# adc_microboard.net
KiCad netlist of a schematic drawn in EAGLE
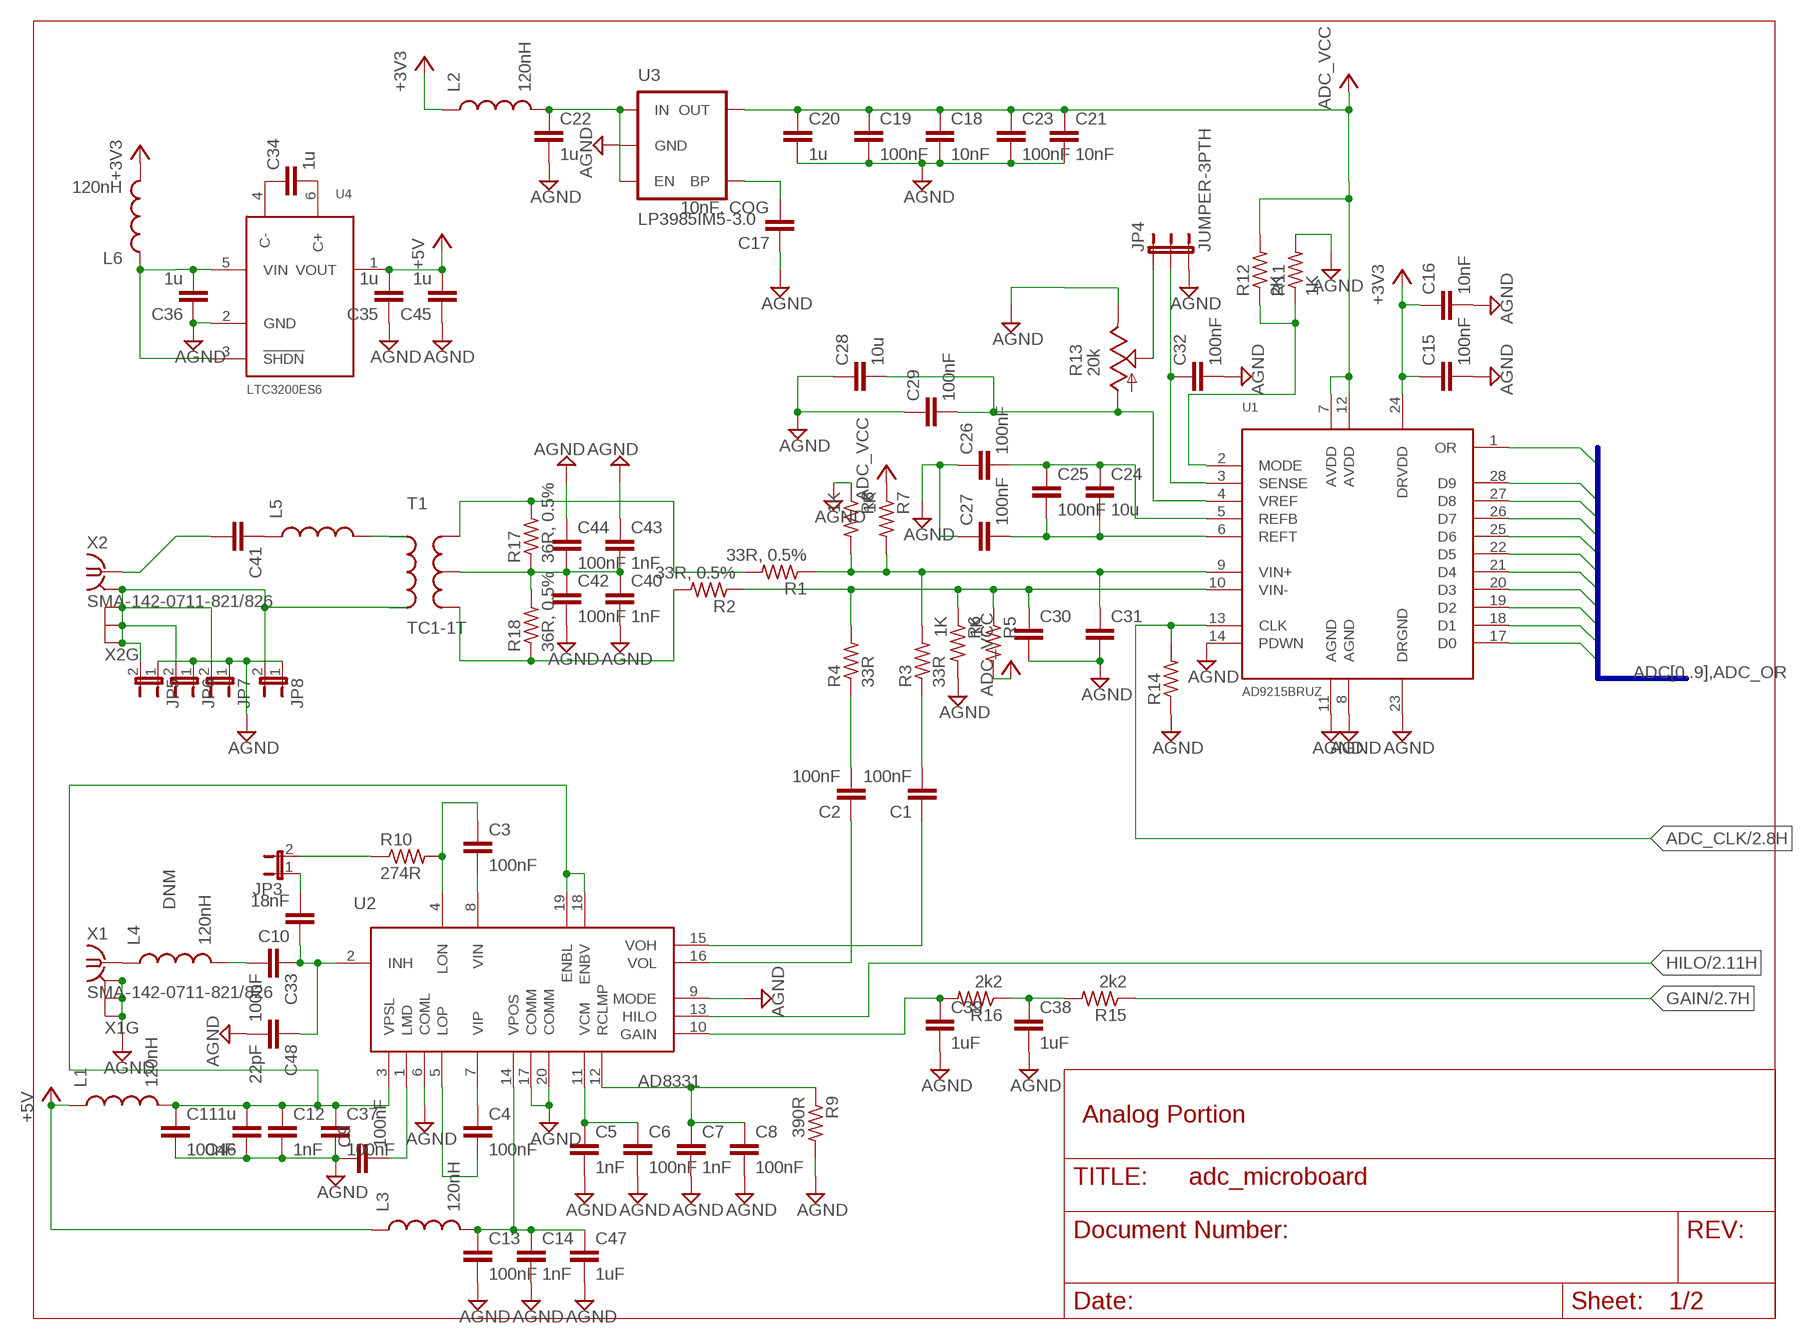
[diagram p0: schematic, sheet 1]
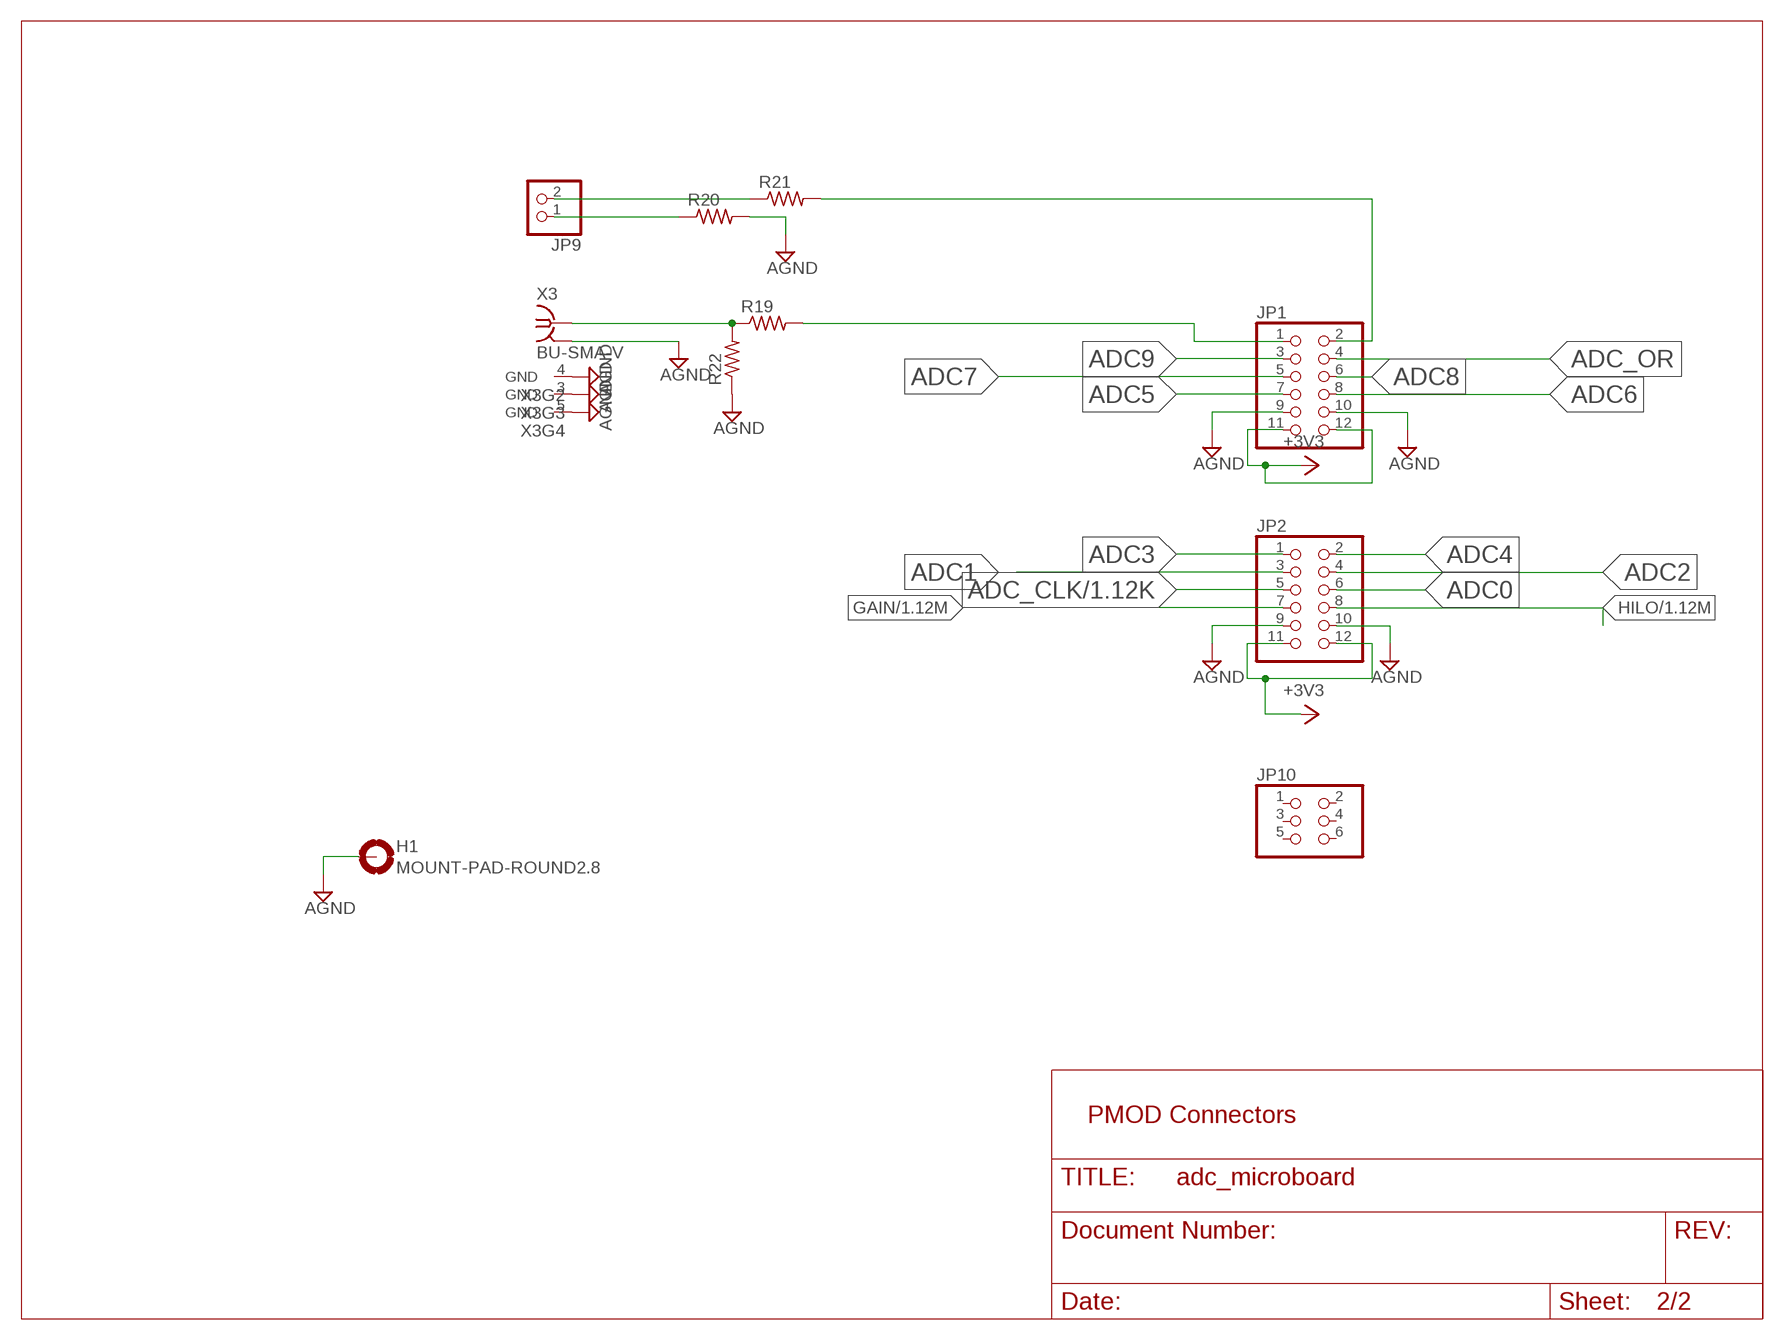
[diagram p1: schematic, sheet 2]

(export (version "E")
  (design (tool "Eeschema 10.0.6"))
  (components
    (comp (ref "C1")
      (value "100nF")
      (footprint "eagle-import:C0603K")
      (libsource (lib "eagle-import") (part "C-EUC0603K"))
    )
    (comp (ref "C2")
      (value "100nF")
      (footprint "eagle-import:C0603K")
      (libsource (lib "eagle-import") (part "C-EUC0603K"))
    )
    (comp (ref "C3")
      (value "100nF")
      (footprint "eagle-import:C0402")
      (libsource (lib "eagle-import") (part "C-EUC0402"))
    )
    (comp (ref "C4")
      (value "100nF")
      (footprint "eagle-import:C0402")
      (libsource (lib "eagle-import") (part "C-EUC0402"))
    )
    (comp (ref "C5")
      (value "1nF")
      (footprint "eagle-import:C0402")
      (fields (field (name "PART#") "C1005X7R1E102K"))
      (libsource (lib "eagle-import") (part "C-EUC0402"))
    )
    (comp (ref "C6")
      (value "100nF")
      (footprint "eagle-import:C0402")
      (fields (field (name "PART#") "GRM155R61A104KA01D"))
      (libsource (lib "eagle-import") (part "C-EUC0402"))
    )
    (comp (ref "C7")
      (value "1nF")
      (footprint "eagle-import:C0402")
      (fields (field (name "PART#") "C1005X7R1E102K"))
      (libsource (lib "eagle-import") (part "C-EUC0402"))
    )
    (comp (ref "C8")
      (value "100nF")
      (footprint "eagle-import:C0402")
      (fields (field (name "PART#") "GRM155R61A104KA01D"))
      (libsource (lib "eagle-import") (part "C-EUC0402"))
    )
    (comp (ref "C9")
      (value "100nF")
      (footprint "eagle-import:C0402")
      (fields (field (name "PART#") "GRM155R61A104KA01D"))
      (libsource (lib "eagle-import") (part "C-EUC0402"))
    )
    (comp (ref "C10")
      (value "18nF")
      (footprint "eagle-import:C0603")
      (libsource (lib "eagle-import") (part "C-EUC0603"))
    )
    (comp (ref "C11")
      (value "100nF")
      (footprint "eagle-import:C0402")
      (fields (field (name "PART#") "GRM155R61A104KA01D"))
      (libsource (lib "eagle-import") (part "C-EUC0402"))
    )
    (comp (ref "C12")
      (value "1nF")
      (footprint "eagle-import:C0402")
      (fields (field (name "PART#") "C1005X7R1E102K"))
      (libsource (lib "eagle-import") (part "C-EUC0402"))
    )
    (comp (ref "C13")
      (value "100nF")
      (footprint "eagle-import:C0402")
      (fields (field (name "PART#") "GRM155R61A104KA01D"))
      (libsource (lib "eagle-import") (part "C-EUC0402"))
    )
    (comp (ref "C14")
      (value "1nF")
      (footprint "eagle-import:C0402")
      (fields (field (name "PART#") "C1005X7R1E102K"))
      (libsource (lib "eagle-import") (part "C-EUC0402"))
    )
    (comp (ref "C15")
      (value "100nF")
      (footprint "eagle-import:C0402")
      (fields (field (name "PART#") "GRM155R61A104KA01D"))
      (libsource (lib "eagle-import") (part "C-EUC0402"))
    )
    (comp (ref "C16")
      (value "10nF")
      (footprint "eagle-import:C0402")
      (libsource (lib "eagle-import") (part "C-EUC0402"))
    )
    (comp (ref "C17")
      (value "10nF, COG")
      (footprint "eagle-import:C0402")
      (libsource (lib "eagle-import") (part "C-EUC0402"))
    )
    (comp (ref "C18")
      (value "10nF")
      (footprint "eagle-import:C0402")
      (fields (field (name "PART#") "GRM155R71E103KA01D"))
      (libsource (lib "eagle-import") (part "C-EUC0402"))
    )
    (comp (ref "C19")
      (value "100nF")
      (footprint "eagle-import:C0402")
      (fields (field (name "PART#") "GRM155R61A104KA01D"))
      (libsource (lib "eagle-import") (part "C-EUC0402"))
    )
    (comp (ref "C20")
      (value "1u")
      (footprint "eagle-import:C0603")
      (fields (field (name "PART#") "GRM188R61A105KA61D"))
      (libsource (lib "eagle-import") (part "C-EUC0603"))
    )
    (comp (ref "C21")
      (value "10nF")
      (footprint "eagle-import:C0402")
      (fields (field (name "PART#") "GRM155R71E103KA01D"))
      (libsource (lib "eagle-import") (part "C-EUC0402"))
    )
    (comp (ref "C22")
      (value "1u")
      (footprint "eagle-import:C0603")
      (fields (field (name "PART#") "GRM188R61A105KA61D"))
      (libsource (lib "eagle-import") (part "C-EUC0603"))
    )
    (comp (ref "C23")
      (value "100nF")
      (footprint "eagle-import:C0402")
      (fields (field (name "PART#") "GRM155R61A104KA01D"))
      (libsource (lib "eagle-import") (part "C-EUC0402"))
    )
    (comp (ref "C24")
      (value "10u")
      (footprint "eagle-import:C0603")
      (libsource (lib "eagle-import") (part "C-EUC0603"))
    )
    (comp (ref "C25")
      (value "100nF")
      (footprint "eagle-import:C0402")
      (fields (field (name "PART#") "GRM155R61A104KA01D"))
      (libsource (lib "eagle-import") (part "C-EUC0402"))
    )
    (comp (ref "C26")
      (value "100nF")
      (footprint "eagle-import:C0402")
      (fields (field (name "PART#") "GRM155R61A104KA01D"))
      (libsource (lib "eagle-import") (part "C-EUC0402"))
    )
    (comp (ref "C27")
      (value "100nF")
      (footprint "eagle-import:C0402")
      (fields (field (name "PART#") "GRM155R61A104KA01D"))
      (libsource (lib "eagle-import") (part "C-EUC0402"))
    )
    (comp (ref "C28")
      (value "10u")
      (footprint "eagle-import:C0603")
      (libsource (lib "eagle-import") (part "C-EUC0603"))
    )
    (comp (ref "C29")
      (value "100nF")
      (footprint "eagle-import:C0402")
      (fields (field (name "PART#") "GRM155R61A104KA01D"))
      (libsource (lib "eagle-import") (part "C-EUC0402"))
    )
    (comp (ref "C30")
      (value "C-EUC0402")
      (footprint "eagle-import:C0402")
      (libsource (lib "eagle-import") (part "C-EUC0402"))
    )
    (comp (ref "C31")
      (value "C-EUC0402")
      (footprint "eagle-import:C0402")
      (libsource (lib "eagle-import") (part "C-EUC0402"))
    )
    (comp (ref "C32")
      (value "100nF")
      (footprint "eagle-import:C0402")
      (fields (field (name "PART#") "GRM155R61A104KA01D"))
      (libsource (lib "eagle-import") (part "C-EUC0402"))
    )
    (comp (ref "C33")
      (value "100nF")
      (footprint "eagle-import:C0603K")
      (libsource (lib "eagle-import") (part "C-EUC0603K"))
    )
    (comp (ref "C34")
      (value "1u")
      (footprint "eagle-import:C0603")
      (fields (field (name "PART#") "GRM188R61A105KA61D"))
      (libsource (lib "eagle-import") (part "C-EUC0603"))
    )
    (comp (ref "C35")
      (value "1u")
      (footprint "eagle-import:C0603")
      (fields (field (name "PART#") "GRM188R61A105KA61D"))
      (libsource (lib "eagle-import") (part "C-EUC0603"))
    )
    (comp (ref "C36")
      (value "1u")
      (footprint "eagle-import:C0603")
      (fields (field (name "PART#") "GRM188R61A105KA61D"))
      (libsource (lib "eagle-import") (part "C-EUC0603"))
    )
    (comp (ref "C37")
      (value "100nF")
      (footprint "eagle-import:C0402")
      (fields (field (name "PART#") "GRM155R61A104KA01D"))
      (libsource (lib "eagle-import") (part "C-EUC0402"))
    )
    (comp (ref "C38")
      (value "1uF")
      (footprint "eagle-import:C0603")
      (libsource (lib "eagle-import") (part "C-EUC0603"))
    )
    (comp (ref "C39")
      (value "1uF")
      (footprint "eagle-import:C0603")
      (libsource (lib "eagle-import") (part "C-EUC0603"))
    )
    (comp (ref "C40")
      (value "1nF")
      (footprint "eagle-import:C0402")
      (fields (field (name "PART#") "C1005X7R1E102K"))
      (libsource (lib "eagle-import") (part "C-EUC0402"))
    )
    (comp (ref "C41")
      (value "C-EUC0603K")
      (footprint "eagle-import:C0603K")
      (libsource (lib "eagle-import") (part "C-EUC0603K"))
    )
    (comp (ref "C42")
      (value "100nF")
      (footprint "eagle-import:C0402")
      (fields (field (name "PART#") "GRM155R61A104KA01D"))
      (libsource (lib "eagle-import") (part "C-EUC0402"))
    )
    (comp (ref "C43")
      (value "1nF")
      (footprint "eagle-import:C0402")
      (fields (field (name "PART#") "C1005X7R1E102K"))
      (libsource (lib "eagle-import") (part "C-EUC0402"))
    )
    (comp (ref "C44")
      (value "100nF")
      (footprint "eagle-import:C0402")
      (fields (field (name "PART#") "GRM155R61A104KA01D"))
      (libsource (lib "eagle-import") (part "C-EUC0402"))
    )
    (comp (ref "C45")
      (value "1u")
      (footprint "eagle-import:C0603")
      (fields (field (name "PART#") "GRM188R61A105KA61D"))
      (libsource (lib "eagle-import") (part "C-EUC0603"))
    )
    (comp (ref "C46")
      (value "1u")
      (footprint "eagle-import:C0402")
      (fields (field (name "PART#") "GRM188R61A105KA61D"))
      (libsource (lib "eagle-import") (part "C-EUC0402"))
    )
    (comp (ref "C47")
      (value "1uF")
      (footprint "eagle-import:C0402")
      (fields (field (name "PART#") "C1005X7R1E102K"))
      (libsource (lib "eagle-import") (part "C-EUC0402"))
    )
    (comp (ref "C48")
      (value "22pF")
      (footprint "eagle-import:C0603")
      (libsource (lib "eagle-import") (part "C-EUC0603"))
    )
    (comp (ref "JP3")
      (value "JUMPER-2SMD-NC")
      (footprint "eagle-import:SJ_2S")
      (libsource (lib "eagle-import") (part "JUMPER-2SMD-NC"))
    )
    (comp (ref "JP4")
      (value "JUMPER-3PTH")
      (footprint "eagle-import:1X03")
      (libsource (lib "eagle-import") (part "JUMPER-3PTH"))
    )
    (comp (ref "JP5")
      (value "JUMPER-2SMD-NC")
      (footprint "eagle-import:SJ_2S")
      (libsource (lib "eagle-import") (part "JUMPER-2SMD-NC"))
    )
    (comp (ref "JP6")
      (value "JUMPER-2SMD-NC")
      (footprint "eagle-import:SJ_2S")
      (libsource (lib "eagle-import") (part "JUMPER-2SMD-NC"))
    )
    (comp (ref "JP7")
      (value "JUMPER-2SMD-NC")
      (footprint "eagle-import:SJ_2S")
      (libsource (lib "eagle-import") (part "JUMPER-2SMD-NC"))
    )
    (comp (ref "JP8")
      (value "JUMPER-2SMD-NC")
      (footprint "eagle-import:SJ_2S")
      (libsource (lib "eagle-import") (part "JUMPER-2SMD-NC"))
    )
    (comp (ref "L1")
      (value "120nH")
      (footprint "eagle-import:0603")
      (fields (field (name "PART#") "MLF1608DR12M"))
      (libsource (lib "eagle-import") (part "INDUCTOR0603"))
    )
    (comp (ref "L2")
      (value "120nH")
      (footprint "eagle-import:0603")
      (libsource (lib "eagle-import") (part "INDUCTOR0603"))
    )
    (comp (ref "L3")
      (value "120nH")
      (footprint "eagle-import:0603")
      (libsource (lib "eagle-import") (part "INDUCTOR0603"))
    )
    (comp (ref "L4")
      (value "120nH")
      (footprint "eagle-import:0603")
      (libsource (lib "eagle-import") (part "INDUCTOR0603"))
    )
    (comp (ref "L5")
      (value "INDUCTOR0603")
      (footprint "eagle-import:0603")
      (libsource (lib "eagle-import") (part "INDUCTOR0603"))
    )
    (comp (ref "L6")
      (value "120nH")
      (footprint "eagle-import:0603")
      (libsource (lib "eagle-import") (part "INDUCTOR0603"))
    )
    (comp (ref "R1")
      (value "33R, 0.5%")
      (footprint "eagle-import:R0603")
      (libsource (lib "eagle-import") (part "R-US_R0603"))
    )
    (comp (ref "R2")
      (value "33R, 0.5%")
      (footprint "eagle-import:R0603")
      (libsource (lib "eagle-import") (part "R-US_R0603"))
    )
    (comp (ref "R3")
      (value "33R")
      (footprint "eagle-import:R0603")
      (libsource (lib "eagle-import") (part "R-US_R0603"))
    )
    (comp (ref "R4")
      (value "33R")
      (footprint "eagle-import:R0603")
      (libsource (lib "eagle-import") (part "R-US_R0603"))
    )
    (comp (ref "R5")
      (value "1K")
      (footprint "eagle-import:R0402")
      (libsource (lib "eagle-import") (part "R-US_R0402"))
    )
    (comp (ref "R6")
      (value "1K")
      (footprint "eagle-import:R0402")
      (libsource (lib "eagle-import") (part "R-US_R0402"))
    )
    (comp (ref "R7")
      (value "1K")
      (footprint "eagle-import:R0402")
      (libsource (lib "eagle-import") (part "R-US_R0402"))
    )
    (comp (ref "R8")
      (value "1K")
      (footprint "eagle-import:R0402")
      (libsource (lib "eagle-import") (part "R-US_R0402"))
    )
    (comp (ref "R9")
      (value "390R")
      (footprint "eagle-import:R0603")
      (libsource (lib "eagle-import") (part "R-US_R0603"))
    )
    (comp (ref "R10")
      (value "274R")
      (footprint "eagle-import:R0603")
      (libsource (lib "eagle-import") (part "R-US_R0603"))
    )
    (comp (ref "R11")
      (value "1K")
      (footprint "eagle-import:R0402")
      (libsource (lib "eagle-import") (part "R-US_R0402"))
    )
    (comp (ref "R12")
      (value "2K")
      (footprint "eagle-import:R0603")
      (libsource (lib "eagle-import") (part "R-US_R0603"))
    )
    (comp (ref "R13")
      (value "20k")
      (footprint "eagle-import:3361P")
      (fields (field (name "PART#") "3361P-1-203GLF"))
      (libsource (lib "eagle-import") (part "TRIM_US-3361P"))
    )
    (comp (ref "R14")
      (value "R-US_R0603")
      (footprint "eagle-import:R0603")
      (libsource (lib "eagle-import") (part "R-US_R0603"))
    )
    (comp (ref "R15")
      (value "2k2")
      (footprint "eagle-import:R0603")
      (libsource (lib "eagle-import") (part "R-US_R0603"))
    )
    (comp (ref "R16")
      (value "2k2")
      (footprint "eagle-import:R0603")
      (libsource (lib "eagle-import") (part "R-US_R0603"))
    )
    (comp (ref "R17")
      (value "36R, 0.5%")
      (footprint "eagle-import:R0603")
      (libsource (lib "eagle-import") (part "R-US_R0603"))
    )
    (comp (ref "R18")
      (value "36R, 0.5%")
      (footprint "eagle-import:R0603")
      (libsource (lib "eagle-import") (part "R-US_R0603"))
    )
    (comp (ref "T1")
      (value "TC1-1T")
      (footprint "eagle-import:AT224-1A")
      (libsource (lib "eagle-import") (part "TC1-1T"))
    )
    (comp (ref "U1")
      (value "AD9215BRUZ")
      (footprint "eagle-import:TSSOP28")
      (libsource (lib "eagle-import") (part "AD9215BRUZ"))
    )
    (comp (ref "U2")
      (value "AD8331")
      (footprint "eagle-import:QSOP20")
      (fields (field (name "PART#") "AD8331ARQZ"))
      (libsource (lib "eagle-import") (part "AD8331"))
    )
    (comp (ref "U3")
      (value "LP3985IM5-3.0")
      (footprint "eagle-import:SOT23-5")
      (libsource (lib "eagle-import") (part "V_REG_LDOSMD"))
    )
    (comp (ref "U4")
      (value "LTC3200ES6")
      (footprint "eagle-import:SOT23-6L")
      (fields (field (name "PART#") "LTC3200ES6-5#TRMPBF"))
      (libsource (lib "eagle-import") (part "LTC3200ES6"))
    )
    (comp (ref "X1")
      (value "SMA-142-0711-821/826")
      (footprint "eagle-import:J502-ND-142-0711-821_826")
      (fields
        (field (name "MF") "JOHNSON COMPONENTS")
        (field (name "MPN") "142-0711-821")
        (field (name "DIGIKEY#") "CONSMA003.062-ND")
      )
      (libsource (lib "eagle-import") (part "SMA-142-0711-821/826"))
    )
    (comp (ref "X2")
      (value "SMA-142-0711-821/826")
      (footprint "eagle-import:J502-ND-142-0711-821_826")
      (fields
        (field (name "MF") "JOHNSON COMPONENTS")
        (field (name "MPN") "142-0711-821")
        (field (name "DIGIKEY#") "CONSMA003.062-ND")
      )
      (libsource (lib "eagle-import") (part "SMA-142-0711-821/826"))
    )
    (comp (ref "H1")
      (value "MOUNT-PAD-ROUND2.8")
      (footprint "eagle-import:2,8-PAD")
      (libsource (lib "eagle-import") (part "MOUNT-PAD-ROUND2.8"))
    )
    (comp (ref "JP1")
      (value "PINHD-2X6")
      (footprint "eagle-import:2X06")
      (libsource (lib "eagle-import") (part "PINHD-2X6"))
    )
    (comp (ref "JP2")
      (value "PINHD-2X6")
      (footprint "eagle-import:2X06")
      (libsource (lib "eagle-import") (part "PINHD-2X6"))
    )
    (comp (ref "JP9")
      (value "PINHD-1X2/90")
      (footprint "eagle-import:1X02_90")
      (libsource (lib "eagle-import") (part "PINHD-1X2/90"))
    )
    (comp (ref "JP10")
      (value "PINHD-2X3")
      (footprint "eagle-import:2X03")
      (libsource (lib "eagle-import") (part "PINHD-2X3"))
    )
    (comp (ref "R19")
      (value "R-US_R0603")
      (footprint "eagle-import:R0603")
      (libsource (lib "eagle-import") (part "R-US_R0603"))
    )
    (comp (ref "R20")
      (value "R-US_R0603")
      (footprint "eagle-import:R0603")
      (libsource (lib "eagle-import") (part "R-US_R0603"))
    )
    (comp (ref "R21")
      (value "R-US_R0603")
      (footprint "eagle-import:R0603")
      (libsource (lib "eagle-import") (part "R-US_R0603"))
    )
    (comp (ref "R22")
      (value "R-US_R0603")
      (footprint "eagle-import:R0603")
      (libsource (lib "eagle-import") (part "R-US_R0603"))
    )
    (comp (ref "X3")
      (value "BU-SMA-V")
      (footprint "eagle-import:BU-SMA-V")
      (libsource (lib "eagle-import") (part "BU-SMA-V"))
    )
  )
  (nets
    (net (code "1") (name "+3V3") (class "Default")
      (node (ref "C15") (pin "1") (pinfunction "1_1") (pintype "passive"))
      (node (ref "C16") (pin "1") (pinfunction "1_1") (pintype "passive"))
      (node (ref "JP1") (pin "11") (pinfunction "11_11") (pintype "passive"))
      (node (ref "JP1") (pin "12") (pinfunction "12_12") (pintype "passive"))
      (node (ref "JP2") (pin "11") (pinfunction "11_11") (pintype "passive"))
      (node (ref "JP2") (pin "12") (pinfunction "12_12") (pintype "passive"))
      (node (ref "L2") (pin "1") (pinfunction "1_1") (pintype "passive"))
      (node (ref "L6") (pin "2") (pinfunction "2_2") (pintype "passive"))
      (node (ref "U1") (pin "24") (pinfunction "DRVDD_24") (pintype "bidirectional"))
    )
    (net (code "2") (name "+5V") (class "Default")
      (node (ref "C35") (pin "2") (pinfunction "2_2") (pintype "passive"))
      (node (ref "C45") (pin "2") (pinfunction "2_2") (pintype "passive"))
      (node (ref "L1") (pin "1") (pinfunction "1_1") (pintype "passive"))
      (node (ref "L3") (pin "1") (pinfunction "1_1") (pintype "passive"))
      (node (ref "U4") (pin "1") (pinfunction "VOUT_1") (pintype "bidirectional"))
    )
    (net (code "4") (name "ADC0") (class "Default")
      (node (ref "JP2") (pin "6") (pinfunction "6_6") (pintype "passive"))
      (node (ref "U1") (pin "17") (pinfunction "D0_17") (pintype "bidirectional"))
    )
    (net (code "5") (name "ADC1") (class "Default")
      (node (ref "JP2") (pin "3") (pinfunction "3_3") (pintype "passive"))
      (node (ref "U1") (pin "18") (pinfunction "D1_18") (pintype "bidirectional"))
    )
    (net (code "6") (name "ADC2") (class "Default")
      (node (ref "JP2") (pin "4") (pinfunction "4_4") (pintype "passive"))
      (node (ref "U1") (pin "19") (pinfunction "D2_19") (pintype "bidirectional"))
    )
    (net (code "7") (name "ADC3") (class "Default")
      (node (ref "JP2") (pin "1") (pinfunction "1_1") (pintype "passive"))
      (node (ref "U1") (pin "20") (pinfunction "D3_20") (pintype "bidirectional"))
    )
    (net (code "8") (name "ADC4") (class "Default")
      (node (ref "JP2") (pin "2") (pinfunction "2_2") (pintype "passive"))
      (node (ref "U1") (pin "21") (pinfunction "D4_21") (pintype "bidirectional"))
    )
    (net (code "9") (name "ADC5") (class "Default")
      (node (ref "JP1") (pin "7") (pinfunction "7_7") (pintype "passive"))
      (node (ref "U1") (pin "22") (pinfunction "D5_22") (pintype "bidirectional"))
    )
    (net (code "10") (name "ADC6") (class "Default")
      (node (ref "JP1") (pin "8") (pinfunction "8_8") (pintype "passive"))
      (node (ref "U1") (pin "25") (pinfunction "D6_25") (pintype "bidirectional"))
    )
    (net (code "11") (name "ADC7") (class "Default")
      (node (ref "JP1") (pin "5") (pinfunction "5_5") (pintype "passive"))
      (node (ref "U1") (pin "26") (pinfunction "D7_26") (pintype "bidirectional"))
    )
    (net (code "12") (name "ADC8") (class "Default")
      (node (ref "JP1") (pin "6") (pinfunction "6_6") (pintype "passive"))
      (node (ref "U1") (pin "27") (pinfunction "D8_27") (pintype "bidirectional"))
    )
    (net (code "13") (name "ADC9") (class "Default")
      (node (ref "JP1") (pin "3") (pinfunction "3_3") (pintype "passive"))
      (node (ref "U1") (pin "28") (pinfunction "D9_28") (pintype "bidirectional"))
    )
    (net (code "14") (name "ADC_CLK") (class "Default")
      (node (ref "JP2") (pin "5") (pinfunction "5_5") (pintype "passive"))
      (node (ref "R14") (pin "2") (pinfunction "2_2") (pintype "passive"))
      (node (ref "U1") (pin "13") (pinfunction "CLK_13") (pintype "bidirectional"))
    )
    (net (code "15") (name "ADC_OR") (class "Default")
      (node (ref "JP1") (pin "4") (pinfunction "4_4") (pintype "passive"))
      (node (ref "U1") (pin "1") (pinfunction "OR_1") (pintype "bidirectional"))
    )
    (net (code "16") (name "ADC_VCC") (class "Default")
      (node (ref "C18") (pin "1") (pinfunction "1_1") (pintype "passive"))
      (node (ref "C19") (pin "1") (pinfunction "1_1") (pintype "passive"))
      (node (ref "C20") (pin "1") (pinfunction "1_1") (pintype "passive"))
      (node (ref "C21") (pin "1") (pinfunction "1_1") (pintype "passive"))
      (node (ref "C23") (pin "1") (pinfunction "1_1") (pintype "passive"))
      (node (ref "R12") (pin "2") (pinfunction "2_2") (pintype "passive"))
      (node (ref "R5") (pin "2") (pinfunction "2_2") (pintype "passive"))
      (node (ref "R7") (pin "1") (pinfunction "1_1") (pintype "passive"))
      (node (ref "U1") (pin "12") (pinfunction "AVDD_12") (pintype "bidirectional"))
      (node (ref "U1") (pin "7") (pinfunction "AVDD_7") (pintype "bidirectional"))
      (node (ref "U3") (pin "5") (pinfunction "OUT_5") (pintype "passive"))
    )
    (net (code "17") (name "AGND") (class "Default")
      (node (ref "C11") (pin "2") (pinfunction "2_2") (pintype "passive"))
      (node (ref "C12") (pin "2") (pinfunction "2_2") (pintype "passive"))
      (node (ref "C13") (pin "2") (pinfunction "2_2") (pintype "passive"))
      (node (ref "C14") (pin "2") (pinfunction "2_2") (pintype "passive"))
      (node (ref "C15") (pin "2") (pinfunction "2_2") (pintype "passive"))
      (node (ref "C16") (pin "2") (pinfunction "2_2") (pintype "passive"))
      (node (ref "C17") (pin "1") (pinfunction "1_1") (pintype "passive"))
      (node (ref "C18") (pin "2") (pinfunction "2_2") (pintype "passive"))
      (node (ref "C19") (pin "2") (pinfunction "2_2") (pintype "passive"))
      (node (ref "C20") (pin "2") (pinfunction "2_2") (pintype "passive"))
      (node (ref "C21") (pin "2") (pinfunction "2_2") (pintype "passive"))
      (node (ref "C22") (pin "2") (pinfunction "2_2") (pintype "passive"))
      (node (ref "C23") (pin "2") (pinfunction "2_2") (pintype "passive"))
      (node (ref "C26") (pin "1") (pinfunction "1_1") (pintype "passive"))
      (node (ref "C27") (pin "1") (pinfunction "1_1") (pintype "passive"))
      (node (ref "C28") (pin "1") (pinfunction "1_1") (pintype "passive"))
      (node (ref "C29") (pin "1") (pinfunction "1_1") (pintype "passive"))
      (node (ref "C30") (pin "2") (pinfunction "2_2") (pintype "passive"))
      (node (ref "C31") (pin "2") (pinfunction "2_2") (pintype "passive"))
      (node (ref "C32") (pin "2") (pinfunction "2_2") (pintype "passive"))
      (node (ref "C35") (pin "1") (pinfunction "1_1") (pintype "passive"))
      (node (ref "C36") (pin "1") (pinfunction "1_1") (pintype "passive"))
      (node (ref "C37") (pin "2") (pinfunction "2_2") (pintype "passive"))
      (node (ref "C38") (pin "2") (pinfunction "2_2") (pintype "passive"))
      (node (ref "C39") (pin "2") (pinfunction "2_2") (pintype "passive"))
      (node (ref "C40") (pin "2") (pinfunction "2_2") (pintype "passive"))
      (node (ref "C42") (pin "2") (pinfunction "2_2") (pintype "passive"))
      (node (ref "C43") (pin "1") (pinfunction "1_1") (pintype "passive"))
      (node (ref "C44") (pin "1") (pinfunction "1_1") (pintype "passive"))
      (node (ref "C45") (pin "1") (pinfunction "1_1") (pintype "passive"))
      (node (ref "C46") (pin "1") (pinfunction "1_1") (pintype "passive"))
      (node (ref "C47") (pin "2") (pinfunction "2_2") (pintype "passive"))
      (node (ref "C48") (pin "2") (pinfunction "2_2") (pintype "passive"))
      (node (ref "C5") (pin "2") (pinfunction "2_2") (pintype "passive"))
      (node (ref "C6") (pin "2") (pinfunction "2_2") (pintype "passive"))
      (node (ref "C7") (pin "2") (pinfunction "2_2") (pintype "passive"))
      (node (ref "C8") (pin "2") (pinfunction "2_2") (pintype "passive"))
      (node (ref "C9") (pin "1") (pinfunction "1_1") (pintype "passive"))
      (node (ref "H1") (pin "B2,8") (pinfunction "MOUNT_B2,8") (pintype "passive"))
      (node (ref "JP1") (pin "10") (pinfunction "10_10") (pintype "passive"))
      (node (ref "JP1") (pin "9") (pinfunction "9_9") (pintype "passive"))
      (node (ref "JP2") (pin "10") (pinfunction "10_10") (pintype "passive"))
      (node (ref "JP2") (pin "9") (pinfunction "9_9") (pintype "passive"))
      (node (ref "JP4") (pin "3") (pinfunction "3_3") (pintype "passive"))
      (node (ref "JP5") (pin "1") (pinfunction "1_1") (pintype "passive"))
      (node (ref "JP6") (pin "1") (pinfunction "1_1") (pintype "passive"))
      (node (ref "JP7") (pin "1") (pinfunction "1_1") (pintype "passive"))
      (node (ref "JP8") (pin "1") (pinfunction "1_1") (pintype "passive"))
      (node (ref "R11") (pin "2") (pinfunction "2_2") (pintype "passive"))
      (node (ref "R13") (pin "1") (pinfunction "E_1") (pintype "passive"))
      (node (ref "R14") (pin "1") (pinfunction "1_1") (pintype "passive"))
      (node (ref "R20") (pin "2") (pinfunction "2_2") (pintype "passive"))
      (node (ref "R22") (pin "1") (pinfunction "1_1") (pintype "passive"))
      (node (ref "R6") (pin "2") (pinfunction "2_2") (pintype "passive"))
      (node (ref "R8") (pin "1") (pinfunction "1_1") (pintype "passive"))
      (node (ref "R9") (pin "2") (pinfunction "2_2") (pintype "passive"))
      (node (ref "U1") (pin "11") (pinfunction "AGND_11") (pintype "bidirectional"))
      (node (ref "U1") (pin "14") (pinfunction "PDWN_14") (pintype "bidirectional"))
      (node (ref "U1") (pin "23") (pinfunction "DRGND_23") (pintype "bidirectional"))
      (node (ref "U1") (pin "8") (pinfunction "AGND_8") (pintype "bidirectional"))
      (node (ref "U2") (pin "17") (pinfunction "COMM_17") (pintype "bidirectional"))
      (node (ref "U2") (pin "20") (pinfunction "COMM_20") (pintype "bidirectional"))
      (node (ref "U2") (pin "6") (pinfunction "COML_6") (pintype "bidirectional"))
      (node (ref "U2") (pin "9") (pinfunction "MODE_9") (pintype "bidirectional"))
      (node (ref "U3") (pin "2") (pinfunction "GND_2") (pintype "input"))
      (node (ref "U4") (pin "2") (pinfunction "GND_2") (pintype "bidirectional"))
      (node (ref "X1") (pin "G@1") (pinfunction "GND_G@1") (pintype "power_in"))
      (node (ref "X1") (pin "G@2") (pinfunction "GND_G@2") (pintype "power_in"))
      (node (ref "X1") (pin "G@3") (pinfunction "GND_G@3") (pintype "power_in"))
      (node (ref "X1") (pin "G@4") (pinfunction "GND_G@4") (pintype "power_in"))
      (node (ref "X3") (pin "2") (pinfunction "GND_2") (pintype "power_in"))
      (node (ref "X3") (pin "3") (pinfunction "GND_3") (pintype "power_in"))
      (node (ref "X3") (pin "4") (pinfunction "GND_4") (pintype "power_in"))
      (node (ref "X3") (pin "5") (pinfunction "GND_5") (pintype "power_in"))
    )
    (net (code "18") (name "GAIN") (class "Default")
      (node (ref "JP2") (pin "7") (pinfunction "7_7") (pintype "passive"))
      (node (ref "R15") (pin "1") (pinfunction "1_1") (pintype "passive"))
    )
    (net (code "19") (name "HILO") (class "Default")
      (node (ref "JP2") (pin "8") (pinfunction "8_8") (pintype "passive"))
      (node (ref "U2") (pin "13") (pinfunction "HILO_13") (pintype "bidirectional"))
    )
    (net (code "20") (name "Net-(C1-Pad2)") (class "Default")
      (node (ref "C1") (pin "2") (pinfunction "2_2") (pintype "passive"))
      (node (ref "R3") (pin "1") (pinfunction "1_1") (pintype "passive"))
    )
    (net (code "21") (name "Net-(C2-Pad2)") (class "Default")
      (node (ref "C2") (pin "2") (pinfunction "2_2") (pintype "passive"))
      (node (ref "R4") (pin "1") (pinfunction "1_1") (pintype "passive"))
    )
    (net (code "22") (name "Net-(C10-Pad2)") (class "Default")
      (node (ref "C10") (pin "2") (pinfunction "2_2") (pintype "passive"))
      (node (ref "JP3") (pin "1") (pinfunction "1_1") (pintype "passive"))
    )
    (net (code "23") (name "Net-(C33-Pad2)") (class "Default")
      (node (ref "C33") (pin "2") (pinfunction "2_2") (pintype "passive"))
      (node (ref "L4") (pin "2") (pinfunction "2_2") (pintype "passive"))
    )
    (net (code "24") (name "Net-(C38-Pad1)") (class "Default")
      (node (ref "C38") (pin "1") (pinfunction "1_1") (pintype "passive"))
      (node (ref "R15") (pin "2") (pinfunction "2_2") (pintype "passive"))
      (node (ref "R16") (pin "1") (pinfunction "1_1") (pintype "passive"))
    )
    (net (code "25") (name "Net-(C41-Pad1)") (class "Default")
      (node (ref "C41") (pin "1") (pinfunction "1_1") (pintype "passive"))
      (node (ref "L5") (pin "1") (pinfunction "1_1") (pintype "passive"))
    )
    (net (code "26") (name "Net-(C41-Pad2)") (class "Default")
      (node (ref "C41") (pin "2") (pinfunction "2_2") (pintype "passive"))
      (node (ref "X2") (pin "1") (pinfunction "1_1") (pintype "passive"))
    )
    (net (code "27") (name "Net-(JP1-Pad1)") (class "Default")
      (node (ref "JP1") (pin "1") (pinfunction "1_1") (pintype "passive"))
      (node (ref "R19") (pin "2") (pinfunction "2_2") (pintype "passive"))
    )
    (net (code "28") (name "Net-(JP1-Pad2)") (class "Default")
      (node (ref "JP1") (pin "2") (pinfunction "2_2") (pintype "passive"))
      (node (ref "R21") (pin "2") (pinfunction "2_2") (pintype "passive"))
    )
    (net (code "29") (name "Net-(JP3-Pad2)") (class "Default")
      (node (ref "JP3") (pin "2") (pinfunction "2_2") (pintype "passive"))
      (node (ref "R10") (pin "1") (pinfunction "1_1") (pintype "passive"))
    )
    (net (code "30") (name "Net-(JP9-Pad1)") (class "Default")
      (node (ref "JP9") (pin "1") (pinfunction "1_1") (pintype "passive"))
      (node (ref "R20") (pin "1") (pinfunction "1_1") (pintype "passive"))
    )
    (net (code "31") (name "Net-(JP9-Pad2)") (class "Default")
      (node (ref "JP9") (pin "2") (pinfunction "2_2") (pintype "passive"))
      (node (ref "R21") (pin "1") (pinfunction "1_1") (pintype "passive"))
    )
    (net (code "32") (name "Net-(L4-Pad1)") (class "Default")
      (node (ref "L4") (pin "1") (pinfunction "1_1") (pintype "passive"))
      (node (ref "X1") (pin "1") (pinfunction "1_1") (pintype "passive"))
    )
    (net (code "33") (name "Net-(R13-A)") (class "Default")
      (node (ref "C28") (pin "2") (pinfunction "2_2") (pintype "passive"))
      (node (ref "C29") (pin "2") (pinfunction "2_2") (pintype "passive"))
      (node (ref "R13") (pin "3") (pinfunction "A_3") (pintype "passive"))
      (node (ref "U1") (pin "4") (pinfunction "VREF_4") (pintype "bidirectional"))
    )
    (net (code "34") (name "Net-(R13-S)") (class "Default")
      (node (ref "JP4") (pin "1") (pinfunction "1_1") (pintype "passive"))
      (node (ref "R13") (pin "2") (pinfunction "S_2") (pintype "passive"))
    )
    (net (code "35") (name "Net-(R19-Pad1)") (class "Default")
      (node (ref "R19") (pin "1") (pinfunction "1_1") (pintype "passive"))
      (node (ref "R22") (pin "2") (pinfunction "2_2") (pintype "passive"))
      (node (ref "X3") (pin "1") (pinfunction "1_1") (pintype "passive"))
    )
    (net (code "36") (name "Net-(T1-P1)") (class "Default")
      (node (ref "L5") (pin "2") (pinfunction "2_2") (pintype "passive"))
      (node (ref "T1") (pin "6") (pinfunction "P1_6") (pintype "passive"))
    )
    (net (code "37") (name "Net-(T1-P2)") (class "Default")
      (node (ref "JP5") (pin "2") (pinfunction "2_2") (pintype "passive"))
      (node (ref "JP6") (pin "2") (pinfunction "2_2") (pintype "passive"))
      (node (ref "JP7") (pin "2") (pinfunction "2_2") (pintype "passive"))
      (node (ref "JP8") (pin "2") (pinfunction "2_2") (pintype "passive"))
      (node (ref "T1") (pin "4") (pinfunction "P2_4") (pintype "passive"))
      (node (ref "X2") (pin "G@1") (pinfunction "GND_G@1") (pintype "power_in"))
      (node (ref "X2") (pin "G@2") (pinfunction "GND_G@2") (pintype "power_in"))
      (node (ref "X2") (pin "G@3") (pinfunction "GND_G@3") (pintype "power_in"))
      (node (ref "X2") (pin "G@4") (pinfunction "GND_G@4") (pintype "power_in"))
    )
    (net (code "38") (name "Net-(T1-S1)") (class "Default")
      (node (ref "R1") (pin "2") (pinfunction "2_2") (pintype "passive"))
      (node (ref "R17") (pin "2") (pinfunction "2_2") (pintype "passive"))
      (node (ref "T1") (pin "1") (pinfunction "S1_1") (pintype "passive"))
    )
    (net (code "39") (name "Net-(T1-S2)") (class "Default")
      (node (ref "R18") (pin "1") (pinfunction "1_1") (pintype "passive"))
      (node (ref "R2") (pin "2") (pinfunction "2_2") (pintype "passive"))
      (node (ref "T1") (pin "3") (pinfunction "S2_3") (pintype "passive"))
    )
    (net (code "40") (name "Net-(T1-ST)") (class "Default")
      (node (ref "C40") (pin "1") (pinfunction "1_1") (pintype "passive"))
      (node (ref "C42") (pin "1") (pinfunction "1_1") (pintype "passive"))
      (node (ref "C43") (pin "2") (pinfunction "2_2") (pintype "passive"))
      (node (ref "C44") (pin "2") (pinfunction "2_2") (pintype "passive"))
      (node (ref "R17") (pin "1") (pinfunction "1_1") (pintype "passive"))
      (node (ref "R18") (pin "2") (pinfunction "2_2") (pintype "passive"))
      (node (ref "T1") (pin "2") (pinfunction "ST_2") (pintype "passive"))
    )
    (net (code "41") (name "Net-(U1-MODE)") (class "Default")
      (node (ref "R11") (pin "1") (pinfunction "1_1") (pintype "passive"))
      (node (ref "R12") (pin "1") (pinfunction "1_1") (pintype "passive"))
      (node (ref "U1") (pin "2") (pinfunction "MODE_2") (pintype "bidirectional"))
    )
    (net (code "42") (name "Net-(U1-REFB)") (class "Default")
      (node (ref "C24") (pin "1") (pinfunction "1_1") (pintype "passive"))
      (node (ref "C25") (pin "1") (pinfunction "1_1") (pintype "passive"))
      (node (ref "C26") (pin "2") (pinfunction "2_2") (pintype "passive"))
      (node (ref "U1") (pin "5") (pinfunction "REFB_5") (pintype "bidirectional"))
    )
    (net (code "43") (name "Net-(U1-REFT)") (class "Default")
      (node (ref "C24") (pin "2") (pinfunction "2_2") (pintype "passive"))
      (node (ref "C25") (pin "2") (pinfunction "2_2") (pintype "passive"))
      (node (ref "C27") (pin "2") (pinfunction "2_2") (pintype "passive"))
      (node (ref "U1") (pin "6") (pinfunction "REFT_6") (pintype "bidirectional"))
    )
    (net (code "44") (name "Net-(U1-SENSE)") (class "Default")
      (node (ref "C32") (pin "1") (pinfunction "1_1") (pintype "passive"))
      (node (ref "JP4") (pin "2") (pinfunction "2_2") (pintype "passive"))
      (node (ref "U1") (pin "3") (pinfunction "SENSE_3") (pintype "bidirectional"))
    )
    (net (code "45") (name "Net-(U1-VIN+)") (class "Default")
      (node (ref "C31") (pin "1") (pinfunction "1_1") (pintype "passive"))
      (node (ref "R1") (pin "1") (pinfunction "1_1") (pintype "passive"))
      (node (ref "R3") (pin "2") (pinfunction "2_2") (pintype "passive"))
      (node (ref "R7") (pin "2") (pinfunction "2_2") (pintype "passive"))
      (node (ref "R8") (pin "2") (pinfunction "2_2") (pintype "passive"))
      (node (ref "U1") (pin "9") (pinfunction "VIN+_9") (pintype "bidirectional"))
    )
    (net (code "46") (name "Net-(U1-VIN-)") (class "Default")
      (node (ref "C30") (pin "1") (pinfunction "1_1") (pintype "passive"))
      (node (ref "R2") (pin "1") (pinfunction "1_1") (pintype "passive"))
      (node (ref "R4") (pin "2") (pinfunction "2_2") (pintype "passive"))
      (node (ref "R5") (pin "1") (pinfunction "1_1") (pintype "passive"))
      (node (ref "R6") (pin "1") (pinfunction "1_1") (pintype "passive"))
      (node (ref "U1") (pin "10") (pinfunction "VIN-_10") (pintype "bidirectional"))
    )
    (net (code "47") (name "Net-(U2-ENBL)") (class "Default")
      (node (ref "C11") (pin "1") (pinfunction "1_1") (pintype "passive"))
      (node (ref "C12") (pin "1") (pinfunction "1_1") (pintype "passive"))
      (node (ref "C37") (pin "1") (pinfunction "1_1") (pintype "passive"))
      (node (ref "C46") (pin "2") (pinfunction "2_2") (pintype "passive"))
      (node (ref "L1") (pin "2") (pinfunction "2_2") (pintype "passive"))
      (node (ref "U2") (pin "18") (pinfunction "ENBV_18") (pintype "bidirectional"))
      (node (ref "U2") (pin "19") (pinfunction "ENBL_19") (pintype "bidirectional"))
      (node (ref "U2") (pin "3") (pinfunction "VPSL_3") (pintype "bidirectional"))
    )
    (net (code "48") (name "Net-(U2-GAIN)") (class "Default")
      (node (ref "C39") (pin "1") (pinfunction "1_1") (pintype "passive"))
      (node (ref "R16") (pin "2") (pinfunction "2_2") (pintype "passive"))
      (node (ref "U2") (pin "10") (pinfunction "GAIN_10") (pintype "bidirectional"))
    )
    (net (code "49") (name "Net-(U2-INH)") (class "Default")
      (node (ref "C10") (pin "1") (pinfunction "1_1") (pintype "passive"))
      (node (ref "C33") (pin "1") (pinfunction "1_1") (pintype "passive"))
      (node (ref "C48") (pin "1") (pinfunction "1_1") (pintype "passive"))
      (node (ref "U2") (pin "2") (pinfunction "INH_2") (pintype "bidirectional"))
    )
    (net (code "50") (name "Net-(U2-LMD)") (class "Default")
      (node (ref "C9") (pin "2") (pinfunction "2_2") (pintype "passive"))
      (node (ref "U2") (pin "1") (pinfunction "LMD_1") (pintype "bidirectional"))
    )
    (net (code "51") (name "Net-(U2-LON)") (class "Default")
      (node (ref "C3") (pin "1") (pinfunction "1_1") (pintype "passive"))
      (node (ref "R10") (pin "2") (pinfunction "2_2") (pintype "passive"))
      (node (ref "U2") (pin "4") (pinfunction "LON_4") (pintype "bidirectional"))
    )
    (net (code "52") (name "Net-(U2-LOP)") (class "Default")
      (node (ref "C4") (pin "2") (pinfunction "2_2") (pintype "passive"))
      (node (ref "U2") (pin "5") (pinfunction "LOP_5") (pintype "bidirectional"))
    )
    (net (code "53") (name "Net-(U2-RCLMP)") (class "Default")
      (node (ref "C7") (pin "1") (pinfunction "1_1") (pintype "passive"))
      (node (ref "C8") (pin "1") (pinfunction "1_1") (pintype "passive"))
      (node (ref "R9") (pin "1") (pinfunction "1_1") (pintype "passive"))
      (node (ref "U2") (pin "12") (pinfunction "RCLMP_12") (pintype "bidirectional"))
    )
    (net (code "54") (name "Net-(U2-VCM)") (class "Default")
      (node (ref "C5") (pin "1") (pinfunction "1_1") (pintype "passive"))
      (node (ref "C6") (pin "1") (pinfunction "1_1") (pintype "passive"))
      (node (ref "U2") (pin "11") (pinfunction "VCM_11") (pintype "bidirectional"))
    )
    (net (code "55") (name "Net-(U2-VIN)") (class "Default")
      (node (ref "C3") (pin "2") (pinfunction "2_2") (pintype "passive"))
      (node (ref "U2") (pin "8") (pinfunction "VIN_8") (pintype "bidirectional"))
    )
    (net (code "56") (name "Net-(U2-VIP)") (class "Default")
      (node (ref "C4") (pin "1") (pinfunction "1_1") (pintype "passive"))
      (node (ref "U2") (pin "7") (pinfunction "VIP_7") (pintype "bidirectional"))
    )
    (net (code "57") (name "Net-(U2-VOH)") (class "Default")
      (node (ref "C1") (pin "1") (pinfunction "1_1") (pintype "passive"))
      (node (ref "U2") (pin "15") (pinfunction "VOH_15") (pintype "bidirectional"))
    )
    (net (code "58") (name "Net-(U2-VOL)") (class "Default")
      (node (ref "C2") (pin "1") (pinfunction "1_1") (pintype "passive"))
      (node (ref "U2") (pin "16") (pinfunction "VOL_16") (pintype "bidirectional"))
    )
    (net (code "59") (name "Net-(U2-VPOS)") (class "Default")
      (node (ref "C13") (pin "1") (pinfunction "1_1") (pintype "passive"))
      (node (ref "C14") (pin "1") (pinfunction "1_1") (pintype "passive"))
      (node (ref "C47") (pin "1") (pinfunction "1_1") (pintype "passive"))
      (node (ref "L3") (pin "2") (pinfunction "2_2") (pintype "passive"))
      (node (ref "U2") (pin "14") (pinfunction "VPOS_14") (pintype "bidirectional"))
    )
    (net (code "60") (name "Net-(U3-BP)") (class "Default")
      (node (ref "C17") (pin "2") (pinfunction "2_2") (pintype "passive"))
      (node (ref "U3") (pin "4") (pinfunction "BP_4") (pintype "input"))
    )
    (net (code "61") (name "Net-(U3-EN)") (class "Default")
      (node (ref "C22") (pin "1") (pinfunction "1_1") (pintype "passive"))
      (node (ref "L2") (pin "2") (pinfunction "2_2") (pintype "passive"))
      (node (ref "U3") (pin "1") (pinfunction "IN_1") (pintype "input"))
      (node (ref "U3") (pin "3") (pinfunction "EN_3") (pintype "input"))
    )
    (net (code "62") (name "Net-(U4-C+)") (class "Default")
      (node (ref "C34") (pin "2") (pinfunction "2_2") (pintype "passive"))
      (node (ref "U4") (pin "6") (pinfunction "C+_6") (pintype "bidirectional"))
    )
    (net (code "63") (name "Net-(U4-C-)") (class "Default")
      (node (ref "C34") (pin "1") (pinfunction "1_1") (pintype "passive"))
      (node (ref "U4") (pin "4") (pinfunction "C-_4") (pintype "bidirectional"))
    )
    (net (code "64") (name "Net-(U4-VIN)") (class "Default")
      (node (ref "C36") (pin "2") (pinfunction "2_2") (pintype "passive"))
      (node (ref "L6") (pin "1") (pinfunction "1_1") (pintype "passive"))
      (node (ref "U4") (pin "3") (pinfunction "~{SHDN}_3") (pintype "bidirectional"))
      (node (ref "U4") (pin "5") (pinfunction "VIN_5") (pintype "bidirectional"))
    )
    (net (code "65") (name "unconnected-(JP10-Pad1)") (class "Default")
      (node (ref "JP10") (pin "1") (pinfunction "1_1") (pintype "passive"))
    )
    (net (code "66") (name "unconnected-(JP10-Pad2)") (class "Default")
      (node (ref "JP10") (pin "2") (pinfunction "2_2") (pintype "passive"))
    )
    (net (code "67") (name "unconnected-(JP10-Pad3)") (class "Default")
      (node (ref "JP10") (pin "3") (pinfunction "3_3") (pintype "passive"))
    )
    (net (code "68") (name "unconnected-(JP10-Pad4)") (class "Default")
      (node (ref "JP10") (pin "4") (pinfunction "4_4") (pintype "passive"))
    )
    (net (code "69") (name "unconnected-(JP10-Pad5)") (class "Default")
      (node (ref "JP10") (pin "5") (pinfunction "5_5") (pintype "passive"))
    )
    (net (code "70") (name "unconnected-(JP10-Pad6)") (class "Default")
      (node (ref "JP10") (pin "6") (pinfunction "6_6") (pintype "passive"))
    )
  )
)
